# OLED.net
KiCad netlist of a schematic drawn in Altium Designer
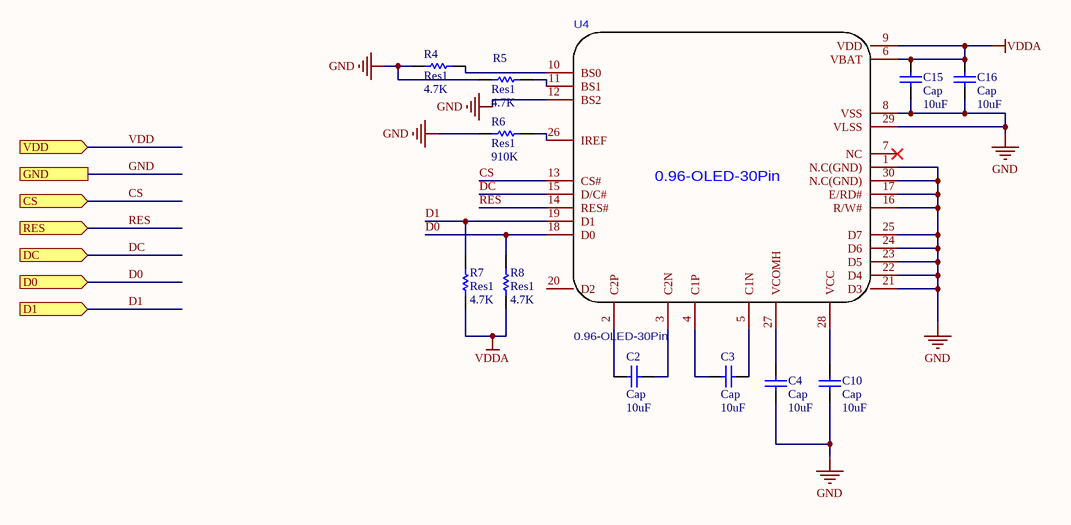
[diagram p0: OLED.SchDoc]

(export (version "E")
  (design (tool "Eeschema 10.0.6"))
  (components
    (comp (ref "C2")
      (value "Cap")
      (footprint "R0603")
      (description "Capacitor")
      (fields (field (name "ALTIUM_VALUE") "10uF") (field (name "PUBLISHER") "Altium Limited"))
      (libsource (lib "Miscellaneous Devices") (part "Cap"))
    )
    (comp (ref "C3")
      (value "Cap")
      (footprint "R0603")
      (description "Capacitor")
      (fields (field (name "ALTIUM_VALUE") "10uF") (field (name "PUBLISHER") "Altium Limited"))
      (libsource (lib "Miscellaneous Devices") (part "Cap"))
    )
    (comp (ref "C4")
      (value "Cap")
      (footprint "R0603")
      (description "Capacitor")
      (fields (field (name "ALTIUM_VALUE") "10uF") (field (name "PUBLISHER") "Altium Limited"))
      (libsource (lib "Miscellaneous Devices") (part "Cap"))
    )
    (comp (ref "C10")
      (value "Cap")
      (footprint "R0603")
      (description "Capacitor")
      (fields (field (name "ALTIUM_VALUE") "10uF") (field (name "PUBLISHER") "Altium Limited"))
      (libsource (lib "Miscellaneous Devices") (part "Cap"))
    )
    (comp (ref "C15")
      (value "Cap")
      (footprint "R0603")
      (description "Capacitor")
      (fields (field (name "ALTIUM_VALUE") "10uF") (field (name "PUBLISHER") "Altium Limited"))
      (libsource (lib "Miscellaneous Devices") (part "Cap"))
    )
    (comp (ref "C16")
      (value "Cap")
      (footprint "R0603")
      (description "Capacitor")
      (fields (field (name "ALTIUM_VALUE") "10uF") (field (name "PUBLISHER") "Altium Limited"))
      (libsource (lib "Miscellaneous Devices") (part "Cap"))
    )
    (comp (ref "R4")
      (value "Res1")
      (footprint "R0603")
      (description "Resistor")
      (fields (field (name "ALTIUM_VALUE") "4.7K") (field (name "PUBLISHER") "Altium Limited"))
      (libsource (lib "Miscellaneous Devices") (part "Res1"))
    )
    (comp (ref "R5")
      (value "Res1")
      (footprint "R0603")
      (description "Resistor")
      (fields (field (name "ALTIUM_VALUE") "4.7K") (field (name "PUBLISHER") "Altium Limited"))
      (libsource (lib "Miscellaneous Devices") (part "Res1"))
    )
    (comp (ref "R6")
      (value "Res1")
      (footprint "R0603")
      (description "Resistor")
      (fields (field (name "ALTIUM_VALUE") "910K") (field (name "PUBLISHER") "Altium Limited"))
      (libsource (lib "Miscellaneous Devices") (part "Res1"))
    )
    (comp (ref "R7")
      (value "Res1")
      (footprint "R0603")
      (description "Resistor")
      (fields (field (name "ALTIUM_VALUE") "4.7K") (field (name "PUBLISHER") "Altium Limited"))
      (libsource (lib "Miscellaneous Devices") (part "Res1"))
    )
    (comp (ref "R8")
      (value "Res1")
      (footprint "R0603")
      (description "Resistor")
      (fields (field (name "ALTIUM_VALUE") "4.7K") (field (name "PUBLISHER") "Altium Limited"))
      (libsource (lib "Miscellaneous Devices") (part "Res1"))
    )
    (comp (ref "U4")
      (value "0.96-OLED-30Pin")
      (footprint "SSD1306")
      (libsource (lib "0.96-OLED-30Pin_2021-09-19") (part "0.96-OLED-30Pin"))
    )
  )
  (nets
    (net (code "1") (name "/CS") (class "Default")
      (node (ref "U4") (pin "13") (pinfunction "CS#_13") (pintype "passive"))
    )
    (net (code "2") (name "/D0") (class "Default")
      (node (ref "R8") (pin "1") (pinfunction "1_1") (pintype "passive"))
      (node (ref "U4") (pin "18") (pinfunction "D0_18") (pintype "passive"))
    )
    (net (code "3") (name "/D1") (class "Default")
      (node (ref "R7") (pin "1") (pinfunction "1_1") (pintype "passive"))
      (node (ref "U4") (pin "19") (pinfunction "D1_19") (pintype "passive"))
    )
    (net (code "4") (name "/DC") (class "Default")
      (node (ref "U4") (pin "15") (pinfunction "D/C#_15") (pintype "passive"))
    )
    (net (code "5") (name "/RES") (class "Default")
      (node (ref "U4") (pin "14") (pinfunction "RES#_14") (pintype "passive"))
    )
    (net (code "7") (name "GND") (class "Default")
      (node (ref "C10") (pin "2") (pinfunction "2_2") (pintype "passive"))
      (node (ref "C15") (pin "2") (pinfunction "2_2") (pintype "passive"))
      (node (ref "C16") (pin "2") (pinfunction "2_2") (pintype "passive"))
      (node (ref "C4") (pin "2") (pinfunction "2_2") (pintype "passive"))
      (node (ref "R4") (pin "2") (pinfunction "2_2") (pintype "passive"))
      (node (ref "R5") (pin "2") (pinfunction "2_2") (pintype "passive"))
      (node (ref "R6") (pin "2") (pinfunction "2_2") (pintype "passive"))
      (node (ref "U4") (pin "1") (pinfunction "N.C(GND)_1") (pintype "passive"))
      (node (ref "U4") (pin "12") (pinfunction "BS2_12") (pintype "passive"))
      (node (ref "U4") (pin "16") (pinfunction "R/W#_16") (pintype "passive"))
      (node (ref "U4") (pin "17") (pinfunction "E/RD#_17") (pintype "passive"))
      (node (ref "U4") (pin "21") (pinfunction "D3_21") (pintype "passive"))
      (node (ref "U4") (pin "22") (pinfunction "D4_22") (pintype "passive"))
      (node (ref "U4") (pin "23") (pinfunction "D5_23") (pintype "passive"))
      (node (ref "U4") (pin "24") (pinfunction "D6_24") (pintype "passive"))
      (node (ref "U4") (pin "25") (pinfunction "D7_25") (pintype "passive"))
      (node (ref "U4") (pin "29") (pinfunction "VLSS_29") (pintype "passive"))
      (node (ref "U4") (pin "30") (pinfunction "N.C(GND)_30") (pintype "passive"))
      (node (ref "U4") (pin "8") (pinfunction "VSS_8") (pintype "passive"))
    )
    (net (code "8") (name "Net-(U4-BS0)") (class "Default")
      (node (ref "R4") (pin "1") (pinfunction "1_1") (pintype "passive"))
      (node (ref "U4") (pin "10") (pinfunction "BS0_10") (pintype "passive"))
    )
    (net (code "9") (name "Net-(U4-BS1)") (class "Default")
      (node (ref "R5") (pin "1") (pinfunction "1_1") (pintype "passive"))
      (node (ref "U4") (pin "11") (pinfunction "BS1_11") (pintype "passive"))
    )
    (net (code "10") (name "Net-(U4-C1N)") (class "Default")
      (node (ref "C3") (pin "1") (pinfunction "1_1") (pintype "passive"))
      (node (ref "U4") (pin "5") (pinfunction "C1N_5") (pintype "passive"))
    )
    (net (code "11") (name "Net-(U4-C1P)") (class "Default")
      (node (ref "C3") (pin "2") (pinfunction "2_2") (pintype "passive"))
      (node (ref "U4") (pin "4") (pinfunction "C1P_4") (pintype "passive"))
    )
    (net (code "12") (name "Net-(U4-C2N)") (class "Default")
      (node (ref "C2") (pin "1") (pinfunction "1_1") (pintype "passive"))
      (node (ref "U4") (pin "3") (pinfunction "C2N_3") (pintype "passive"))
    )
    (net (code "13") (name "Net-(U4-C2P)") (class "Default")
      (node (ref "C2") (pin "2") (pinfunction "2_2") (pintype "passive"))
      (node (ref "U4") (pin "2") (pinfunction "C2P_2") (pintype "passive"))
    )
    (net (code "14") (name "Net-(U4-IREF)") (class "Default")
      (node (ref "R6") (pin "1") (pinfunction "1_1") (pintype "passive"))
      (node (ref "U4") (pin "26") (pinfunction "IREF_26") (pintype "passive"))
    )
    (net (code "15") (name "Net-(U4-VCC)") (class "Default")
      (node (ref "C10") (pin "1") (pinfunction "1_1") (pintype "passive"))
      (node (ref "U4") (pin "28") (pinfunction "VCC_28") (pintype "passive"))
    )
    (net (code "16") (name "Net-(U4-VCOMH)") (class "Default")
      (node (ref "C4") (pin "1") (pinfunction "1_1") (pintype "passive"))
      (node (ref "U4") (pin "27") (pinfunction "VCOMH_27") (pintype "passive"))
    )
    (net (code "17") (name "VDDA") (class "Default")
      (node (ref "C15") (pin "1") (pinfunction "1_1") (pintype "passive"))
      (node (ref "C16") (pin "1") (pinfunction "1_1") (pintype "passive"))
      (node (ref "R7") (pin "2") (pinfunction "2_2") (pintype "passive"))
      (node (ref "R8") (pin "2") (pinfunction "2_2") (pintype "passive"))
      (node (ref "U4") (pin "6") (pinfunction "VBAT_6") (pintype "passive"))
      (node (ref "U4") (pin "9") (pinfunction "VDD_9") (pintype "passive"))
    )
    (net (code "18") (name "unconnected-(U4-D2-Pad20)") (class "Default")
      (node (ref "U4") (pin "20") (pinfunction "D2_20") (pintype "passive"))
    )
    (net (code "19") (name "unconnected-(U4-NC-Pad7)") (class "Default")
      (node (ref "U4") (pin "7") (pinfunction "NC_7") (pintype "passive+no_connect"))
    )
  )
)
